# pearwatch-TOP.net
KiCad netlist of a schematic drawn in EAGLE
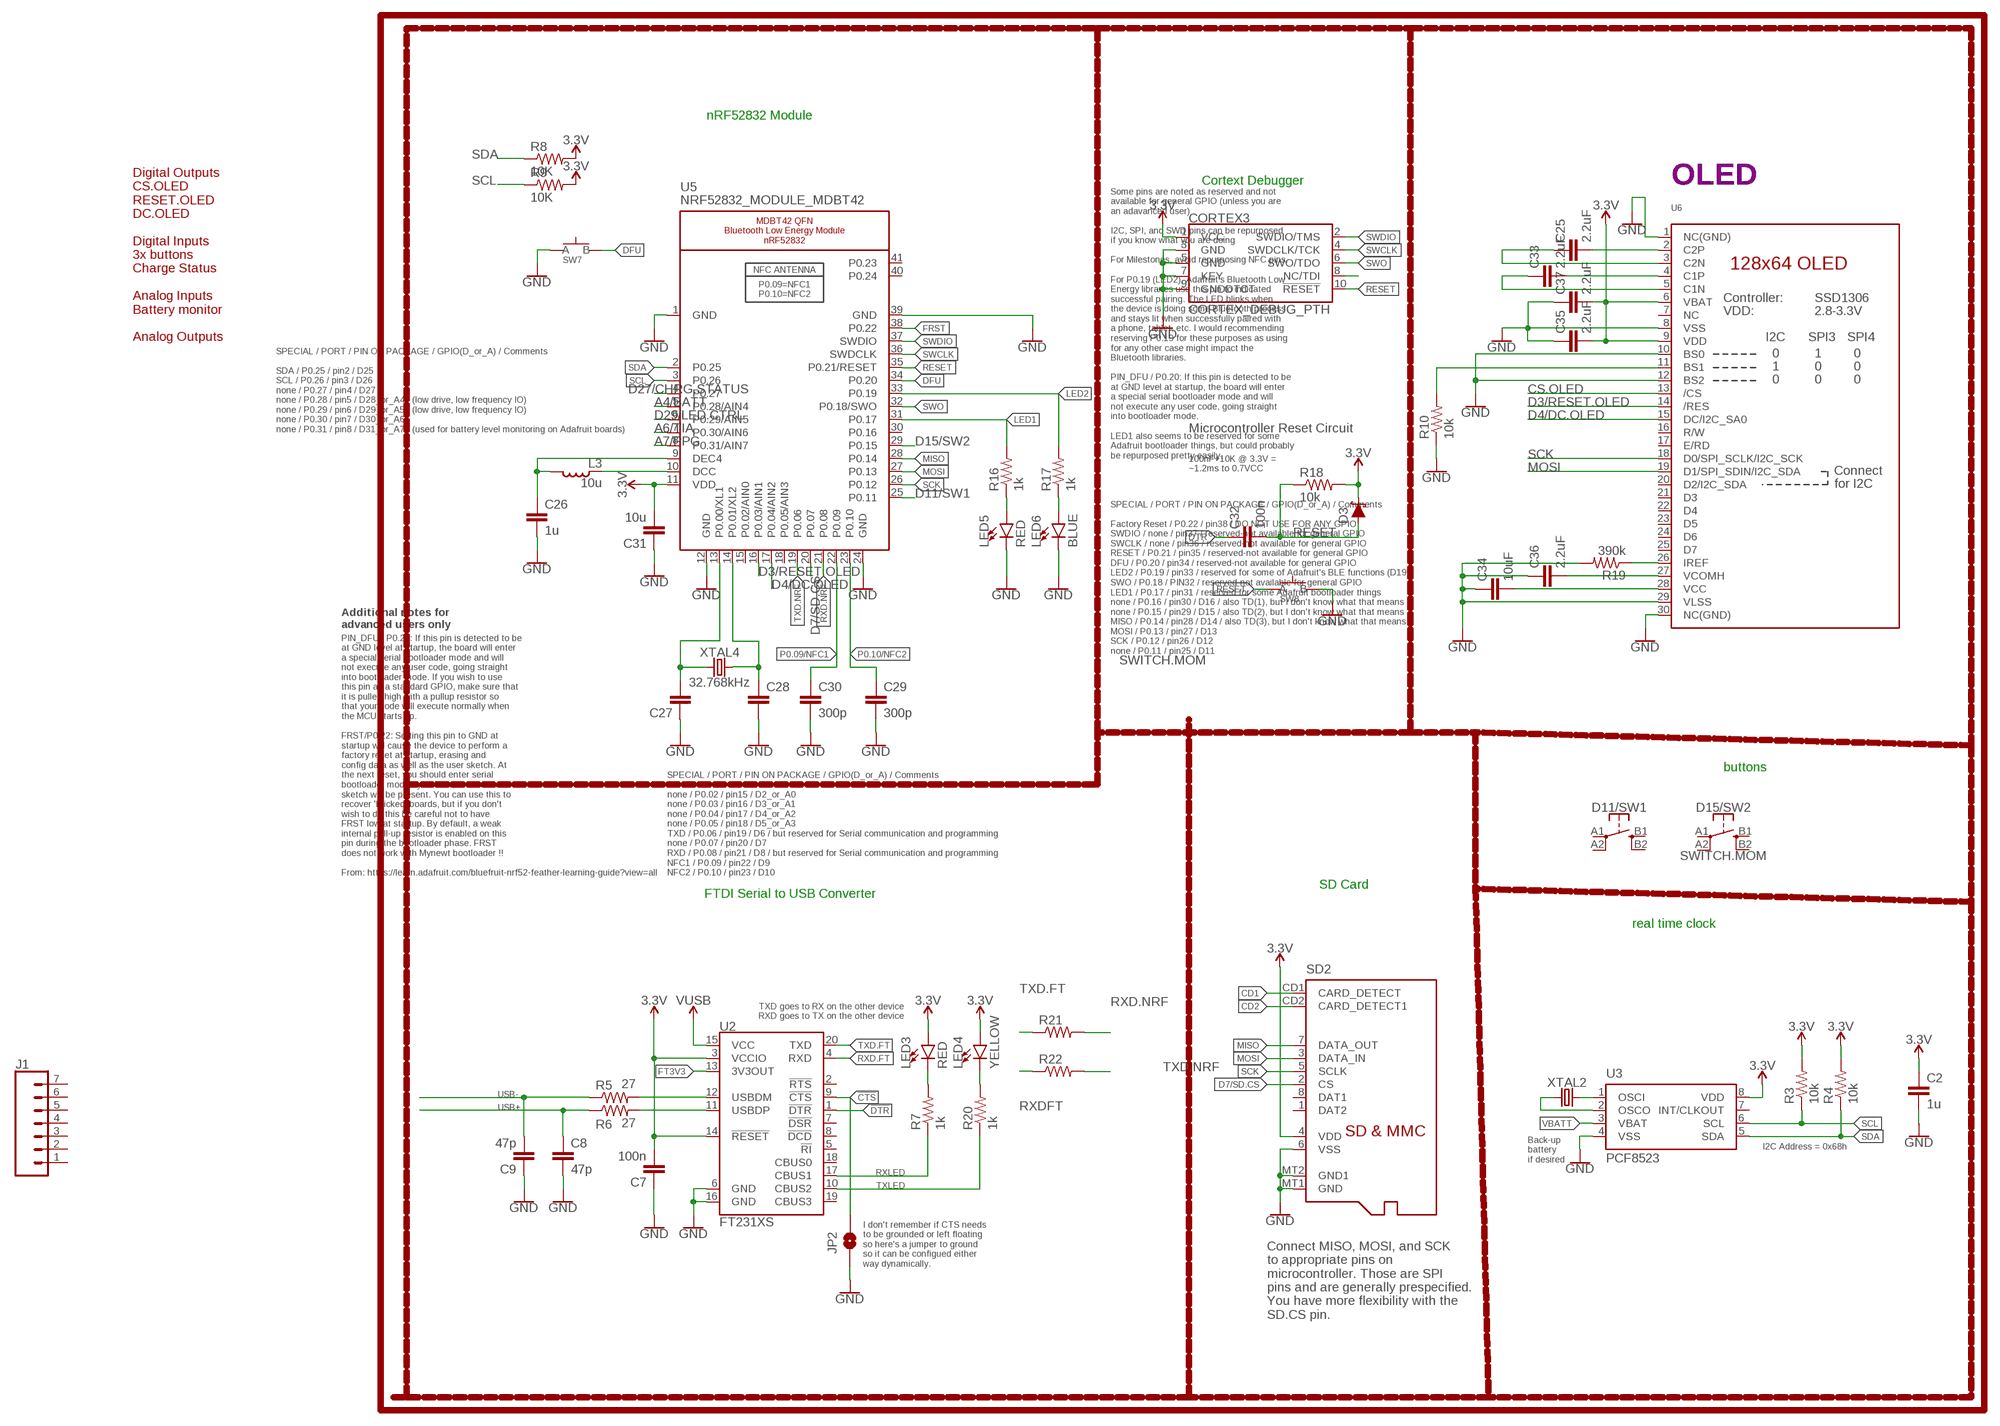
[diagram p0: schematic, sheet 1]

(export (version "E")
  (design (tool "Eeschema 10.0.6"))
  (components
    (comp (ref "C2")
      (value "1u")
      (footprint "eagle-import:C0603")
      (libsource (lib "eagle-import") (part "CAPACITOR0603"))
    )
    (comp (ref "C7")
      (value "100n")
      (footprint "eagle-import:C0603")
      (libsource (lib "eagle-import") (part "CAPACITOR0603"))
    )
    (comp (ref "C8")
      (value "47p")
      (footprint "eagle-import:C0603")
      (libsource (lib "eagle-import") (part "CAPACITOR0603"))
    )
    (comp (ref "C9")
      (value "47p")
      (footprint "eagle-import:C0603")
      (libsource (lib "eagle-import") (part "CAPACITOR0603"))
    )
    (comp (ref "C25")
      (value "2.2uF")
      (footprint "eagle-import:C0402")
      (libsource (lib "eagle-import") (part "CAPACITOR0402"))
    )
    (comp (ref "C26")
      (value "1u")
      (footprint "eagle-import:C0603")
      (libsource (lib "eagle-import") (part "CAPACITOR0603"))
    )
    (comp (ref "C27")
      (value "CAPACITOR0603")
      (footprint "eagle-import:C0603")
      (libsource (lib "eagle-import") (part "CAPACITOR0603"))
    )
    (comp (ref "C28")
      (value "CAPACITOR0603")
      (footprint "eagle-import:C0603")
      (libsource (lib "eagle-import") (part "CAPACITOR0603"))
    )
    (comp (ref "C29")
      (value "300p")
      (footprint "eagle-import:C0603")
      (libsource (lib "eagle-import") (part "CAPACITOR0603"))
    )
    (comp (ref "C30")
      (value "300p")
      (footprint "eagle-import:C0603")
      (libsource (lib "eagle-import") (part "CAPACITOR0603"))
    )
    (comp (ref "C31")
      (value "10u")
      (footprint "eagle-import:C0805")
      (libsource (lib "eagle-import") (part "CAPACITOR0805"))
    )
    (comp (ref "C32")
      (value "100n")
      (footprint "eagle-import:C0603")
      (libsource (lib "eagle-import") (part "CAPACITOR0603"))
    )
    (comp (ref "C33")
      (value "2.2uF")
      (footprint "eagle-import:C0402")
      (libsource (lib "eagle-import") (part "CAPACITOR0402"))
    )
    (comp (ref "C34")
      (value "10uF")
      (footprint "eagle-import:C0603")
      (libsource (lib "eagle-import") (part "CAPACITOR0603"))
    )
    (comp (ref "C35")
      (value "2.2uF")
      (footprint "eagle-import:C0402")
      (libsource (lib "eagle-import") (part "CAPACITOR0402"))
    )
    (comp (ref "C36")
      (value "2.2uF")
      (footprint "eagle-import:C0402")
      (libsource (lib "eagle-import") (part "CAPACITOR0402"))
    )
    (comp (ref "C37")
      (value "2.2uF")
      (footprint "eagle-import:C0402")
      (libsource (lib "eagle-import") (part "CAPACITOR0402"))
    )
    (comp (ref "CORTEX3")
      (value "CORTEX_DEBUG_PTH")
      (footprint "eagle-import:2X5-PTH-1.27MM")
      (libsource (lib "eagle-import") (part "CORTEX_DEBUG_PTH"))
    )
    (comp (ref "D3")
      (value "SCHOTTKY-USC")
      (footprint "eagle-import:USC")
      (libsource (lib "eagle-import") (part "SCHOTTKY-USC"))
    )
    (comp (ref "D11/SW1")
      (value "SWITCH.MOM")
      (footprint "eagle-import:TACTILE_SWITCH_SMD_6.2MM_TALL")
      (libsource (lib "eagle-import") (part "SWITCH.MOM"))
    )
    (comp (ref "D15/SW2")
      (value "SWITCH.MOM")
      (footprint "eagle-import:TACTILE_SWITCH_SMD_6.2MM_TALL")
      (libsource (lib "eagle-import") (part "SWITCH.MOM"))
    )
    (comp (ref "J1")
      (value "CONN_07")
      (footprint "eagle-import:1X07")
      (libsource (lib "eagle-import") (part "CONN_07"))
    )
    (comp (ref "JP2")
      (value "JUMPER-SMT_2_NO_SILK")
      (footprint "eagle-import:SMT-JUMPER_2_NO_SILK")
      (libsource (lib "eagle-import") (part "JUMPER-SMT_2_NO_SILK"))
    )
    (comp (ref "L3")
      (value "10u")
      (footprint "eagle-import:L0603")
      (libsource (lib "eagle-import") (part "INDUCTOR0603"))
    )
    (comp (ref "LED3")
      (value "RED")
      (footprint "eagle-import:LED-0603")
      (libsource (lib "eagle-import") (part "LED0603"))
    )
    (comp (ref "LED4")
      (value "YELLOW")
      (footprint "eagle-import:LED-0603")
      (libsource (lib "eagle-import") (part "LED0603"))
    )
    (comp (ref "LED5")
      (value "RED")
      (footprint "eagle-import:LED-0603")
      (libsource (lib "eagle-import") (part "LED0603"))
    )
    (comp (ref "LED6")
      (value "BLUE")
      (footprint "eagle-import:LED-0603")
      (libsource (lib "eagle-import") (part "LED0603"))
    )
    (comp (ref "R3")
      (value "10k")
      (footprint "eagle-import:R0603")
      (libsource (lib "eagle-import") (part "RESISTOR0603"))
    )
    (comp (ref "R4")
      (value "10k")
      (footprint "eagle-import:R0603")
      (libsource (lib "eagle-import") (part "RESISTOR0603"))
    )
    (comp (ref "R5")
      (value "27")
      (footprint "eagle-import:R0603")
      (libsource (lib "eagle-import") (part "RESISTOR0603"))
    )
    (comp (ref "R6")
      (value "27")
      (footprint "eagle-import:R0603")
      (libsource (lib "eagle-import") (part "RESISTOR0603"))
    )
    (comp (ref "R7")
      (value "1k")
      (footprint "eagle-import:R0603")
      (libsource (lib "eagle-import") (part "RESISTOR0603"))
    )
    (comp (ref "R8")
      (value "10K")
      (footprint "eagle-import:R0603")
      (libsource (lib "eagle-import") (part "RESISTOR0603"))
    )
    (comp (ref "R9")
      (value "10K")
      (footprint "eagle-import:R0603")
      (libsource (lib "eagle-import") (part "RESISTOR0603"))
    )
    (comp (ref "R10")
      (value "10k")
      (footprint "eagle-import:R0603")
      (libsource (lib "eagle-import") (part "RESISTOR0603"))
    )
    (comp (ref "R16")
      (value "1k")
      (footprint "eagle-import:R0603")
      (libsource (lib "eagle-import") (part "RESISTOR0603"))
    )
    (comp (ref "R17")
      (value "1k")
      (footprint "eagle-import:R0603")
      (libsource (lib "eagle-import") (part "RESISTOR0603"))
    )
    (comp (ref "R18")
      (value "10k")
      (footprint "eagle-import:R0603")
      (libsource (lib "eagle-import") (part "RESISTOR0603"))
    )
    (comp (ref "R19")
      (value "390k")
      (footprint "eagle-import:R0603")
      (libsource (lib "eagle-import") (part "RESISTOR0603"))
    )
    (comp (ref "R20")
      (value "1k")
      (footprint "eagle-import:R0603")
      (libsource (lib "eagle-import") (part "RESISTOR0603"))
    )
    (comp (ref "R21")
      (value "RESISTOR0603")
      (footprint "eagle-import:R0603")
      (libsource (lib "eagle-import") (part "RESISTOR0603"))
    )
    (comp (ref "R22")
      (value "RESISTOR0603")
      (footprint "eagle-import:R0603")
      (libsource (lib "eagle-import") (part "RESISTOR0603"))
    )
    (comp (ref "SD2")
      (value "MICROSD")
      (footprint "eagle-import:MICROSD")
      (libsource (lib "eagle-import") (part "MICROSD"))
    )
    (comp (ref "SW7")
      (value "SPST-PTS830GG140-COPY.1-3")
      (footprint "eagle-import:BUTTON-GULLWING")
      (libsource (lib "eagle-import") (part "SPST-PTS830GG140-COPY.1-3"))
    )
    (comp (ref "SW8")
      (value "SPST-PTS830GG140-COPY.1-3")
      (footprint "eagle-import:BUTTON-GULLWING")
      (libsource (lib "eagle-import") (part "SPST-PTS830GG140-COPY.1-3"))
    )
    (comp (ref "U2")
      (value "FT231XS")
      (footprint "eagle-import:SSOP20_L")
      (libsource (lib "eagle-import") (part "FT231XS"))
    )
    (comp (ref "U3")
      (value "PCF8523")
      (footprint "eagle-import:SO8")
      (libsource (lib "eagle-import") (part "PCF8523"))
    )
    (comp (ref "U5")
      (value "NRF52832_MODULE_MDBT42")
      (footprint "eagle-import:BLE_MODULE_RAYTAC_MDBT42")
      (libsource (lib "eagle-import") (part "NRF52832_MODULE_MDBT42"))
    )
    (comp (ref "U6")
      (value "DISP_OLED_UG-2864HSWEG01-NO-WRAPAROUND")
      (footprint "eagle-import:UG-2864HSWEG01_0.96IN_NO-WRAPAROUND")
      (libsource (lib "eagle-import") (part "DISP_OLED_UG-2864HSWEG01-NO-WRAPAROUND"))
    )
    (comp (ref "XTAL2")
      (value "32.7680kHz")
      (footprint "eagle-import:2-SMD.NOLEAD.2.0MMTO1.2MM")
      (fields (field (name "FREQ") "32.7680KHZ"))
      (libsource (lib "eagle-import") (part "CRYSTALECS-.327-12.5-12-C-TR"))
    )
    (comp (ref "XTAL4")
      (value "32.768kHz")
      (footprint "eagle-import:2-SMD.NOLEAD.2.0MMTO1.2MM")
      (libsource (lib "eagle-import") (part "CRYSTALECS-.327-12.5-12-C-TR"))
    )
  )
  (nets
    (net (code "1") (name "/A4{slash}BATT") (class "Default")
      (node (ref "U5") (pin "5") (pinfunction "P0.28/AIN4_5") (pintype "bidirectional"))
    )
    (net (code "2") (name "/A6{slash}TIA") (class "Default")
      (node (ref "U5") (pin "7") (pinfunction "P0.30/AIN6_7") (pintype "bidirectional"))
    )
    (net (code "3") (name "/A7{slash}PPG") (class "Default")
      (node (ref "U5") (pin "8") (pinfunction "P0.31/AIN7_8") (pintype "bidirectional"))
    )
    (net (code "4") (name "/CS.OLED") (class "Default")
      (node (ref "U6") (pin "13") (pinfunction "/CS_13") (pintype "input"))
    )
    (net (code "5") (name "/D3{slash}RESET.OLED") (class "Default")
      (node (ref "U5") (pin "16") (pinfunction "P0.03/AIN1_16") (pintype "bidirectional"))
      (node (ref "U6") (pin "14") (pinfunction "/RES_14") (pintype "input"))
    )
    (net (code "6") (name "/D4{slash}DC.OLED") (class "Default")
      (node (ref "U5") (pin "17") (pinfunction "P0.04/AIN2_17") (pintype "bidirectional"))
      (node (ref "U6") (pin "15") (pinfunction "DC/I2C_SA0_15") (pintype "input"))
    )
    (net (code "7") (name "/D11{slash}SW1") (class "Default")
      (node (ref "U5") (pin "25") (pinfunction "P0.11_25") (pintype "bidirectional"))
    )
    (net (code "8") (name "/D15{slash}SW2") (class "Default")
      (node (ref "U5") (pin "29") (pinfunction "P0.15_29") (pintype "bidirectional"))
    )
    (net (code "9") (name "/D27{slash}CHRG.STATUS") (class "Default")
      (node (ref "U5") (pin "4") (pinfunction "P0.27_4") (pintype "bidirectional"))
    )
    (net (code "10") (name "/D29{slash}LED.CTRL") (class "Default")
      (node (ref "U5") (pin "6") (pinfunction "P0.29/AIN5_6") (pintype "bidirectional"))
    )
    (net (code "11") (name "/RXDFT") (class "Default")
      (node (ref "R22") (pin "1") (pinfunction "1_1") (pintype "passive"))
    )
    (net (code "12") (name "/RXLED") (class "Default")
      (node (ref "R7") (pin "1") (pinfunction "1_1") (pintype "passive"))
      (node (ref "U2") (pin "17") (pinfunction "CBUS1_17") (pintype "bidirectional"))
    )
    (net (code "13") (name "/TXLED") (class "Default")
      (node (ref "R20") (pin "1") (pinfunction "1_1") (pintype "passive"))
      (node (ref "U2") (pin "10") (pinfunction "CBUS2_10") (pintype "bidirectional"))
    )
    (net (code "14") (name "/USB+") (class "Default")
      (node (ref "C8") (pin "1") (pinfunction "1_1") (pintype "passive"))
      (node (ref "R6") (pin "1") (pinfunction "1_1") (pintype "passive"))
    )
    (net (code "15") (name "/USB-") (class "Default")
      (node (ref "C9") (pin "2") (pinfunction "2_2") (pintype "passive"))
      (node (ref "R5") (pin "1") (pinfunction "1_1") (pintype "passive"))
    )
    (net (code "16") (name "/~{CTS}") (class "Default")
      (node (ref "JP2") (pin "2") (pinfunction "2_2") (pintype "passive"))
      (node (ref "U2") (pin "9") (pinfunction "~{CTS}_9") (pintype "bidirectional"))
    )
    (net (code "17") (name "/~{DTR}") (class "Default")
      (node (ref "U2") (pin "1") (pinfunction "~{DTR}_1") (pintype "bidirectional"))
    )
    (net (code "18") (name "3.3V") (class "Default")
      (node (ref "C2") (pin "1") (pinfunction "1_1") (pintype "passive"))
      (node (ref "C31") (pin "2") (pinfunction "2_2") (pintype "passive"))
      (node (ref "C35") (pin "2") (pinfunction "2_2") (pintype "passive"))
      (node (ref "C37") (pin "2") (pinfunction "2_2") (pintype "passive"))
      (node (ref "C7") (pin "2") (pinfunction "2_2") (pintype "passive"))
      (node (ref "CORTEX3") (pin "1") (pinfunction "VCC_1") (pintype "bidirectional"))
      (node (ref "D3") (pin "-") (pinfunction "C_-") (pintype "passive"))
      (node (ref "LED3") (pin "A") (pinfunction "A_A") (pintype "passive"))
      (node (ref "LED4") (pin "A") (pinfunction "A_A") (pintype "passive"))
      (node (ref "R18") (pin "2") (pinfunction "2_2") (pintype "passive"))
      (node (ref "R3") (pin "2") (pinfunction "2_2") (pintype "passive"))
      (node (ref "R4") (pin "2") (pinfunction "2_2") (pintype "passive"))
      (node (ref "R8") (pin "2") (pinfunction "2_2") (pintype "passive"))
      (node (ref "R9") (pin "2") (pinfunction "2_2") (pintype "passive"))
      (node (ref "SD2") (pin "4") (pinfunction "VDD_4") (pintype "power_in"))
      (node (ref "U2") (pin "14") (pinfunction "~{RESET}_14") (pintype "bidirectional"))
      (node (ref "U2") (pin "3") (pinfunction "VCCIO_3") (pintype "bidirectional"))
      (node (ref "U3") (pin "8") (pinfunction "VDD_8") (pintype "power_in"))
      (node (ref "U5") (pin "11") (pinfunction "VDD_11") (pintype "bidirectional"))
      (node (ref "U6") (pin "6") (pinfunction "VBAT_6") (pintype "input"))
      (node (ref "U6") (pin "9") (pinfunction "VDD_9") (pintype "power_in"))
    )
    (net (code "19") (name "CD1") (class "Default")
      (node (ref "SD2") (pin "CD1") (pinfunction "CARD_DETECT_CD1") (pintype "passive"))
    )
    (net (code "20") (name "CD2") (class "Default")
      (node (ref "SD2") (pin "CD2") (pinfunction "CARD_DETECT1_CD2") (pintype "passive"))
    )
    (net (code "21") (name "D7{slash}SD.CS") (class "Default")
      (node (ref "SD2") (pin "2") (pinfunction "CS_2") (pintype "input"))
      (node (ref "U5") (pin "20") (pinfunction "P0.07_20") (pintype "bidirectional"))
    )
    (net (code "22") (name "DFU") (class "Default")
      (node (ref "SW7") (pin "3") (pinfunction "B_3") (pintype "bidirectional"))
      (node (ref "U5") (pin "34") (pinfunction "P0.20_34") (pintype "bidirectional"))
    )
    (net (code "23") (name "DTR") (class "Default")
      (node (ref "C32") (pin "1") (pinfunction "1_1") (pintype "passive"))
    )
    (net (code "24") (name "FRST") (class "Default")
      (node (ref "U5") (pin "38") (pinfunction "P0.22_38") (pintype "bidirectional"))
    )
    (net (code "25") (name "FT3V3") (class "Default")
      (node (ref "U2") (pin "13") (pinfunction "3V3OUT_13") (pintype "bidirectional"))
    )
    (net (code "26") (name "GND") (class "Default")
      (node (ref "C2") (pin "2") (pinfunction "2_2") (pintype "passive"))
      (node (ref "C26") (pin "2") (pinfunction "2_2") (pintype "passive"))
      (node (ref "C27") (pin "1") (pinfunction "1_1") (pintype "passive"))
      (node (ref "C28") (pin "2") (pinfunction "2_2") (pintype "passive"))
      (node (ref "C29") (pin "2") (pinfunction "2_2") (pintype "passive"))
      (node (ref "C30") (pin "2") (pinfunction "2_2") (pintype "passive"))
      (node (ref "C31") (pin "1") (pinfunction "1_1") (pintype "passive"))
      (node (ref "C34") (pin "1") (pinfunction "1_1") (pintype "passive"))
      (node (ref "C35") (pin "1") (pinfunction "1_1") (pintype "passive"))
      (node (ref "C36") (pin "1") (pinfunction "1_1") (pintype "passive"))
      (node (ref "C37") (pin "1") (pinfunction "1_1") (pintype "passive"))
      (node (ref "C7") (pin "1") (pinfunction "1_1") (pintype "passive"))
      (node (ref "C8") (pin "2") (pinfunction "2_2") (pintype "passive"))
      (node (ref "C9") (pin "1") (pinfunction "1_1") (pintype "passive"))
      (node (ref "CORTEX3") (pin "3") (pinfunction "GND_3") (pintype "bidirectional"))
      (node (ref "CORTEX3") (pin "5") (pinfunction "GND_5") (pintype "bidirectional"))
      (node (ref "CORTEX3") (pin "7") (pinfunction "KEY_7") (pintype "bidirectional"))
      (node (ref "CORTEX3") (pin "9") (pinfunction "GNDDTCT_9") (pintype "bidirectional"))
      (node (ref "JP2") (pin "1") (pinfunction "1_1") (pintype "passive"))
      (node (ref "LED5") (pin "C") (pinfunction "C_C") (pintype "passive"))
      (node (ref "LED6") (pin "C") (pinfunction "C_C") (pintype "passive"))
      (node (ref "R10") (pin "1") (pinfunction "1_1") (pintype "passive"))
      (node (ref "R19") (pin "2") (pinfunction "2_2") (pintype "passive"))
      (node (ref "SD2") (pin "6") (pinfunction "VSS_6") (pintype "power_in"))
      (node (ref "SD2") (pin "MT1") (pinfunction "GND_MT1") (pintype "power_in"))
      (node (ref "SD2") (pin "MT2") (pinfunction "GND1_MT2") (pintype "power_in"))
      (node (ref "SW7") (pin "1") (pinfunction "A_1") (pintype "bidirectional"))
      (node (ref "SW8") (pin "3") (pinfunction "B_3") (pintype "bidirectional"))
      (node (ref "U2") (pin "16") (pinfunction "GND_16") (pintype "bidirectional"))
      (node (ref "U2") (pin "6") (pinfunction "GND_6") (pintype "bidirectional"))
      (node (ref "U3") (pin "4") (pinfunction "VSS_4") (pintype "power_in"))
      (node (ref "U5") (pin "1") (pinfunction "GND_1") (pintype "bidirectional"))
      (node (ref "U5") (pin "12") (pinfunction "GND_12") (pintype "bidirectional"))
      (node (ref "U5") (pin "24") (pinfunction "GND_24") (pintype "bidirectional"))
      (node (ref "U5") (pin "39") (pinfunction "GND_39") (pintype "bidirectional"))
      (node (ref "U6") (pin "1") (pinfunction "NC(GND)_1") (pintype "input"))
      (node (ref "U6") (pin "10") (pinfunction "BS0_10") (pintype "input"))
      (node (ref "U6") (pin "12") (pinfunction "BS2_12") (pintype "input"))
      (node (ref "U6") (pin "29") (pinfunction "VLSS_29") (pintype "power_in"))
      (node (ref "U6") (pin "30") (pinfunction "NC(GND)_30") (pintype "input"))
      (node (ref "U6") (pin "8") (pinfunction "VSS_8") (pintype "power_in"))
    )
    (net (code "27") (name "LED1") (class "Default")
      (node (ref "R16") (pin "2") (pinfunction "2_2") (pintype "passive"))
      (node (ref "U5") (pin "31") (pinfunction "P0.17_31") (pintype "bidirectional"))
    )
    (net (code "28") (name "LED2") (class "Default")
      (node (ref "R17") (pin "2") (pinfunction "2_2") (pintype "passive"))
      (node (ref "U5") (pin "33") (pinfunction "P0.19_33") (pintype "bidirectional"))
    )
    (net (code "29") (name "MISO") (class "Default")
      (node (ref "SD2") (pin "7") (pinfunction "DATA_OUT_7") (pintype "output"))
      (node (ref "U5") (pin "28") (pinfunction "P0.14_28") (pintype "bidirectional"))
    )
    (net (code "30") (name "MOSI") (class "Default")
      (node (ref "SD2") (pin "3") (pinfunction "DATA_IN_3") (pintype "input"))
      (node (ref "U5") (pin "27") (pinfunction "P0.13_27") (pintype "bidirectional"))
      (node (ref "U6") (pin "19") (pinfunction "D1/SPI_SDIN/I2C_SDA_19") (pintype "bidirectional"))
    )
    (net (code "31") (name "Net-(LED3-PadC)") (class "Default")
      (node (ref "LED3") (pin "C") (pinfunction "C_C") (pintype "passive"))
      (node (ref "R7") (pin "2") (pinfunction "2_2") (pintype "passive"))
    )
    (net (code "32") (name "Net-(LED4-PadC)") (class "Default")
      (node (ref "LED4") (pin "C") (pinfunction "C_C") (pintype "passive"))
      (node (ref "R20") (pin "2") (pinfunction "2_2") (pintype "passive"))
    )
    (net (code "33") (name "Net-(LED5-PadA)") (class "Default")
      (node (ref "LED5") (pin "A") (pinfunction "A_A") (pintype "passive"))
      (node (ref "R16") (pin "1") (pinfunction "1_1") (pintype "passive"))
    )
    (net (code "34") (name "Net-(LED6-PadA)") (class "Default")
      (node (ref "LED6") (pin "A") (pinfunction "A_A") (pintype "passive"))
      (node (ref "R17") (pin "1") (pinfunction "1_1") (pintype "passive"))
    )
    (net (code "35") (name "Net-(U2-USBDM)") (class "Default")
      (node (ref "R5") (pin "2") (pinfunction "2_2") (pintype "passive"))
      (node (ref "U2") (pin "12") (pinfunction "USBDM_12") (pintype "bidirectional"))
    )
    (net (code "36") (name "Net-(U2-USBDP)") (class "Default")
      (node (ref "R6") (pin "2") (pinfunction "2_2") (pintype "passive"))
      (node (ref "U2") (pin "11") (pinfunction "USBDP_11") (pintype "bidirectional"))
    )
    (net (code "37") (name "Net-(U3-OSCI)") (class "Default")
      (node (ref "U3") (pin "1") (pinfunction "OSCI_1") (pintype "bidirectional"))
      (node (ref "XTAL2") (pin "P$2") (pinfunction "2_P$2") (pintype "passive"))
    )
    (net (code "38") (name "Net-(U3-OSCO)") (class "Default")
      (node (ref "U3") (pin "2") (pinfunction "OSCO_2") (pintype "bidirectional"))
      (node (ref "XTAL2") (pin "P$1") (pinfunction "1_P$1") (pintype "passive"))
    )
    (net (code "39") (name "Net-(U5-DCC)") (class "Default")
      (node (ref "L3") (pin "1") (pinfunction "1_1") (pintype "passive"))
      (node (ref "U5") (pin "10") (pinfunction "DCC_10") (pintype "bidirectional"))
    )
    (net (code "40") (name "Net-(U5-DEC4)") (class "Default")
      (node (ref "C26") (pin "1") (pinfunction "1_1") (pintype "passive"))
      (node (ref "L3") (pin "2") (pinfunction "2_2") (pintype "passive"))
      (node (ref "U5") (pin "9") (pinfunction "DEC4_9") (pintype "bidirectional"))
    )
    (net (code "41") (name "Net-(U5-P0.00{slash}XL1)") (class "Default")
      (node (ref "C27") (pin "2") (pinfunction "2_2") (pintype "passive"))
      (node (ref "U5") (pin "13") (pinfunction "P0.00/XL1_13") (pintype "bidirectional"))
      (node (ref "XTAL4") (pin "P$1") (pinfunction "1_P$1") (pintype "passive"))
    )
    (net (code "42") (name "Net-(U5-P0.01{slash}XL2)") (class "Default")
      (node (ref "C28") (pin "1") (pinfunction "1_1") (pintype "passive"))
      (node (ref "U5") (pin "14") (pinfunction "P0.01/XL2_14") (pintype "bidirectional"))
      (node (ref "XTAL4") (pin "P$2") (pinfunction "2_P$2") (pintype "passive"))
    )
    (net (code "43") (name "Net-(U6-BS1)") (class "Default")
      (node (ref "R10") (pin "2") (pinfunction "2_2") (pintype "passive"))
      (node (ref "U6") (pin "11") (pinfunction "BS1_11") (pintype "input"))
    )
    (net (code "44") (name "Net-(U6-C1N)") (class "Default")
      (node (ref "C33") (pin "1") (pinfunction "1_1") (pintype "passive"))
      (node (ref "U6") (pin "5") (pinfunction "C1N_5") (pintype "input"))
    )
    (net (code "45") (name "Net-(U6-C1P)") (class "Default")
      (node (ref "C33") (pin "2") (pinfunction "2_2") (pintype "passive"))
      (node (ref "U6") (pin "4") (pinfunction "C1P_4") (pintype "input"))
    )
    (net (code "46") (name "Net-(U6-C2N)") (class "Default")
      (node (ref "C25") (pin "1") (pinfunction "1_1") (pintype "passive"))
      (node (ref "U6") (pin "3") (pinfunction "C2N_3") (pintype "input"))
    )
    (net (code "47") (name "Net-(U6-C2P)") (class "Default")
      (node (ref "C25") (pin "2") (pinfunction "2_2") (pintype "passive"))
      (node (ref "U6") (pin "2") (pinfunction "C2P_2") (pintype "input"))
    )
    (net (code "48") (name "Net-(U6-IREF)") (class "Default")
      (node (ref "R19") (pin "1") (pinfunction "1_1") (pintype "passive"))
      (node (ref "U6") (pin "26") (pinfunction "IREF_26") (pintype "input"))
    )
    (net (code "49") (name "Net-(U6-VCC)") (class "Default")
      (node (ref "C34") (pin "2") (pinfunction "2_2") (pintype "passive"))
      (node (ref "U6") (pin "28") (pinfunction "VCC_28") (pintype "power_in"))
    )
    (net (code "50") (name "Net-(U6-VCOMH)") (class "Default")
      (node (ref "C36") (pin "2") (pinfunction "2_2") (pintype "passive"))
      (node (ref "U6") (pin "27") (pinfunction "VCOMH_27") (pintype "output"))
    )
    (net (code "51") (name "P0.09{slash}NFC1") (class "Default")
      (node (ref "C30") (pin "1") (pinfunction "1_1") (pintype "passive"))
      (node (ref "U5") (pin "22") (pinfunction "P0.09_22") (pintype "bidirectional"))
    )
    (net (code "52") (name "P0.10{slash}NFC2") (class "Default")
      (node (ref "C29") (pin "1") (pinfunction "1_1") (pintype "passive"))
      (node (ref "U5") (pin "23") (pinfunction "P0.10_23") (pintype "bidirectional"))
    )
    (net (code "53") (name "RESET") (class "Default")
      (node (ref "C32") (pin "2") (pinfunction "2_2") (pintype "passive"))
      (node (ref "CORTEX3") (pin "10") (pinfunction "~{RESET}_10") (pintype "bidirectional"))
      (node (ref "D3") (pin "+") (pinfunction "A_+") (pintype "passive"))
      (node (ref "R18") (pin "1") (pinfunction "1_1") (pintype "passive"))
      (node (ref "SW8") (pin "1") (pinfunction "A_1") (pintype "bidirectional"))
      (node (ref "U5") (pin "35") (pinfunction "P0.21/RESET_35") (pintype "bidirectional"))
    )
    (net (code "54") (name "RXD.FT") (class "Default")
      (node (ref "U2") (pin "4") (pinfunction "RXD_4") (pintype "bidirectional"))
    )
    (net (code "55") (name "RXD.NRF") (class "Default")
      (node (ref "R21") (pin "2") (pinfunction "2_2") (pintype "passive"))
      (node (ref "U5") (pin "21") (pinfunction "P0.08_21") (pintype "bidirectional"))
    )
    (net (code "56") (name "SCK") (class "Default")
      (node (ref "SD2") (pin "5") (pinfunction "SCLK_5") (pintype "input"))
      (node (ref "U5") (pin "26") (pinfunction "P0.12_26") (pintype "bidirectional"))
      (node (ref "U6") (pin "18") (pinfunction "D0/SPI_SCLK/I2C_SCK_18") (pintype "bidirectional"))
    )
    (net (code "57") (name "SCL") (class "Default")
      (node (ref "R3") (pin "1") (pinfunction "1_1") (pintype "passive"))
      (node (ref "R9") (pin "1") (pinfunction "1_1") (pintype "passive"))
      (node (ref "U3") (pin "6") (pinfunction "SCL_6") (pintype "bidirectional"))
      (node (ref "U5") (pin "3") (pinfunction "P0.26_3") (pintype "bidirectional"))
    )
    (net (code "58") (name "SDA") (class "Default")
      (node (ref "R4") (pin "1") (pinfunction "1_1") (pintype "passive"))
      (node (ref "R8") (pin "1") (pinfunction "1_1") (pintype "passive"))
      (node (ref "U3") (pin "5") (pinfunction "SDA_5") (pintype "bidirectional"))
      (node (ref "U5") (pin "2") (pinfunction "P0.25_2") (pintype "bidirectional"))
    )
    (net (code "59") (name "SWCLK") (class "Default")
      (node (ref "CORTEX3") (pin "4") (pinfunction "SWDCLK/TCK_4") (pintype "bidirectional"))
      (node (ref "U5") (pin "36") (pinfunction "SWDCLK_36") (pintype "bidirectional"))
    )
    (net (code "60") (name "SWDIO") (class "Default")
      (node (ref "CORTEX3") (pin "2") (pinfunction "SWDIO/TMS_2") (pintype "bidirectional"))
      (node (ref "U5") (pin "37") (pinfunction "SWDIO_37") (pintype "bidirectional"))
    )
    (net (code "61") (name "SWO") (class "Default")
      (node (ref "CORTEX3") (pin "6") (pinfunction "SWO/TDO_6") (pintype "bidirectional"))
      (node (ref "U5") (pin "32") (pinfunction "P0.18/SWO_32") (pintype "bidirectional"))
    )
    (net (code "62") (name "TXD.FT") (class "Default")
      (node (ref "R21") (pin "1") (pinfunction "1_1") (pintype "passive"))
      (node (ref "U2") (pin "20") (pinfunction "TXD_20") (pintype "bidirectional"))
    )
    (net (code "63") (name "TXD.NRF") (class "Default")
      (node (ref "R22") (pin "2") (pinfunction "2_2") (pintype "passive"))
      (node (ref "U5") (pin "19") (pinfunction "P0.06_19") (pintype "bidirectional"))
    )
    (net (code "64") (name "VBATT") (class "Default")
      (node (ref "U3") (pin "3") (pinfunction "VBAT_3") (pintype "power_in"))
    )
    (net (code "65") (name "VUSB") (class "Default")
      (node (ref "U2") (pin "15") (pinfunction "VCC_15") (pintype "bidirectional"))
    )
    (net (code "66") (name "unconnected-(CORTEX3-NC{slash}TDI-Pad8)") (class "Default")
      (node (ref "CORTEX3") (pin "8") (pinfunction "NC/TDI_8") (pintype "bidirectional"))
    )
    (net (code "67") (name "unconnected-(D11/SW1-1-PadA1)") (class "Default")
      (node (ref "D11/SW1") (pin "A1") (pinfunction "1_A1") (pintype "passive"))
    )
    (net (code "68") (name "unconnected-(D11/SW1-2-PadA2)") (class "Default")
      (node (ref "D11/SW1") (pin "A2") (pinfunction "2_A2") (pintype "passive"))
    )
    (net (code "69") (name "unconnected-(D11/SW1-3-PadB1)") (class "Default")
      (node (ref "D11/SW1") (pin "B1") (pinfunction "3_B1") (pintype "passive"))
    )
    (net (code "70") (name "unconnected-(D11/SW1-4-PadB2)") (class "Default")
      (node (ref "D11/SW1") (pin "B2") (pinfunction "4_B2") (pintype "passive"))
    )
    (net (code "71") (name "unconnected-(D15/SW2-1-PadA1)") (class "Default")
      (node (ref "D15/SW2") (pin "A1") (pinfunction "1_A1") (pintype "passive"))
    )
    (net (code "72") (name "unconnected-(D15/SW2-2-PadA2)") (class "Default")
      (node (ref "D15/SW2") (pin "A2") (pinfunction "2_A2") (pintype "passive"))
    )
    (net (code "73") (name "unconnected-(D15/SW2-3-PadB1)") (class "Default")
      (node (ref "D15/SW2") (pin "B1") (pinfunction "3_B1") (pintype "passive"))
    )
    (net (code "74") (name "unconnected-(D15/SW2-4-PadB2)") (class "Default")
      (node (ref "D15/SW2") (pin "B2") (pinfunction "4_B2") (pintype "passive"))
    )
    (net (code "75") (name "unconnected-(J1-Pad1)") (class "Default")
      (node (ref "J1") (pin "1") (pinfunction "1_1") (pintype "passive"))
    )
    (net (code "76") (name "unconnected-(J1-Pad2)") (class "Default")
      (node (ref "J1") (pin "2") (pinfunction "2_2") (pintype "passive"))
    )
    (net (code "77") (name "unconnected-(J1-Pad3)") (class "Default")
      (node (ref "J1") (pin "3") (pinfunction "3_3") (pintype "passive"))
    )
    (net (code "78") (name "unconnected-(J1-Pad4)") (class "Default")
      (node (ref "J1") (pin "4") (pinfunction "4_4") (pintype "passive"))
    )
    (net (code "79") (name "unconnected-(J1-Pad5)") (class "Default")
      (node (ref "J1") (pin "5") (pinfunction "5_5") (pintype "passive"))
    )
    (net (code "80") (name "unconnected-(J1-Pad6)") (class "Default")
      (node (ref "J1") (pin "6") (pinfunction "6_6") (pintype "passive"))
    )
    (net (code "81") (name "unconnected-(J1-Pad7)") (class "Default")
      (node (ref "J1") (pin "7") (pinfunction "7_7") (pintype "passive"))
    )
    (net (code "82") (name "unconnected-(SD2-DAT1-Pad8)") (class "Default")
      (node (ref "SD2") (pin "8") (pinfunction "DAT1_8") (pintype "bidirectional"))
    )
    (net (code "83") (name "unconnected-(SD2-DAT2-Pad1)") (class "Default")
      (node (ref "SD2") (pin "1") (pinfunction "DAT2_1") (pintype "bidirectional"))
    )
    (net (code "84") (name "unconnected-(U2-CBUS0-Pad18)") (class "Default")
      (node (ref "U2") (pin "18") (pinfunction "CBUS0_18") (pintype "bidirectional"))
    )
    (net (code "85") (name "unconnected-(U2-CBUS3-Pad19)") (class "Default")
      (node (ref "U2") (pin "19") (pinfunction "CBUS3_19") (pintype "bidirectional"))
    )
    (net (code "86") (name "unconnected-(U2-~{DCD}-Pad8)") (class "Default")
      (node (ref "U2") (pin "8") (pinfunction "~{DCD}_8") (pintype "bidirectional"))
    )
    (net (code "87") (name "unconnected-(U2-~{DSR}-Pad7)") (class "Default")
      (node (ref "U2") (pin "7") (pinfunction "~{DSR}_7") (pintype "bidirectional"))
    )
    (net (code "88") (name "unconnected-(U2-~{RI}-Pad5)") (class "Default")
      (node (ref "U2") (pin "5") (pinfunction "~{RI}_5") (pintype "bidirectional"))
    )
    (net (code "89") (name "unconnected-(U2-~{RTS}-Pad2)") (class "Default")
      (node (ref "U2") (pin "2") (pinfunction "~{RTS}_2") (pintype "bidirectional"))
    )
    (net (code "90") (name "unconnected-(U3-INT{slash}CLKOUT-Pad7)") (class "Default")
      (node (ref "U3") (pin "7") (pinfunction "INT/CLKOUT_7") (pintype "bidirectional"))
    )
    (net (code "91") (name "unconnected-(U5-P0.02{slash}AIN0-Pad15)") (class "Default")
      (node (ref "U5") (pin "15") (pinfunction "P0.02/AIN0_15") (pintype "bidirectional"))
    )
    (net (code "92") (name "unconnected-(U5-P0.05{slash}AIN3-Pad18)") (class "Default")
      (node (ref "U5") (pin "18") (pinfunction "P0.05/AIN3_18") (pintype "bidirectional"))
    )
    (net (code "93") (name "unconnected-(U5-P0.16-Pad30)") (class "Default")
      (node (ref "U5") (pin "30") (pinfunction "P0.16_30") (pintype "bidirectional"))
    )
    (net (code "94") (name "unconnected-(U5-P0.23-Pad41)") (class "Default")
      (node (ref "U5") (pin "41") (pinfunction "P0.23_41") (pintype "bidirectional"))
    )
    (net (code "95") (name "unconnected-(U5-P0.24-Pad40)") (class "Default")
      (node (ref "U5") (pin "40") (pinfunction "P0.24_40") (pintype "bidirectional"))
    )
    (net (code "96") (name "unconnected-(U6-D2{slash}I2C_SDA-Pad20)") (class "Default")
      (node (ref "U6") (pin "20") (pinfunction "D2/I2C_SDA_20") (pintype "bidirectional"))
    )
    (net (code "97") (name "unconnected-(U6-D3-Pad21)") (class "Default")
      (node (ref "U6") (pin "21") (pinfunction "D3_21") (pintype "bidirectional"))
    )
    (net (code "98") (name "unconnected-(U6-D4-Pad22)") (class "Default")
      (node (ref "U6") (pin "22") (pinfunction "D4_22") (pintype "bidirectional"))
    )
    (net (code "99") (name "unconnected-(U6-D5-Pad23)") (class "Default")
      (node (ref "U6") (pin "23") (pinfunction "D5_23") (pintype "bidirectional"))
    )
    (net (code "100") (name "unconnected-(U6-D6-Pad24)") (class "Default")
      (node (ref "U6") (pin "24") (pinfunction "D6_24") (pintype "bidirectional"))
    )
    (net (code "101") (name "unconnected-(U6-D7-Pad25)") (class "Default")
      (node (ref "U6") (pin "25") (pinfunction "D7_25") (pintype "bidirectional"))
    )
    (net (code "102") (name "unconnected-(U6-E{slash}RD-Pad17)") (class "Default")
      (node (ref "U6") (pin "17") (pinfunction "E/RD_17") (pintype "input"))
    )
    (net (code "103") (name "unconnected-(U6-NC-Pad7)") (class "Default")
      (node (ref "U6") (pin "7") (pinfunction "NC_7") (pintype "no_connect"))
    )
    (net (code "104") (name "unconnected-(U6-R{slash}W-Pad16)") (class "Default")
      (node (ref "U6") (pin "16") (pinfunction "R/W_16") (pintype "input"))
    )
  )
)
